# tempSensor.net
KiCad netlist of a schematic drawn in EAGLE
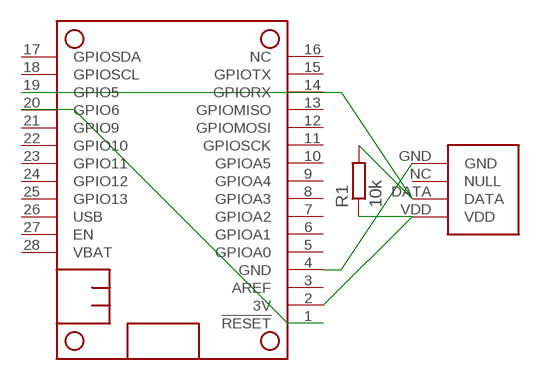
[diagram p0: schematic, sheet 1]

(export (version "E")
  (design (tool "Eeschema 10.0.6"))
  (components
    (comp (ref "MS1")
      (value "FEATHERWING_NODIM")
      (footprint "eagle-import:FEATHERWING_DIM")
      (libsource (lib "eagle-import") (part "FEATHERWING_NODIM"))
    )
    (comp (ref "R1")
      (value "10k")
      (footprint "eagle-import:0207_10")
      (libsource (lib "eagle-import") (part "R-EU_0207/10"))
    )
    (comp (ref "U$1")
      (value "DHT22")
      (footprint "eagle-import:DHT22")
      (libsource (lib "eagle-import") (part "DHT22"))
    )
  )
  (nets
    (net (code "1") (name "/USB") (class "Default")
      (node (ref "MS1") (pin "26") (pinfunction "USB_26") (pintype "power_in"))
    )
    (net (code "2") (name "/VBAT") (class "Default")
      (node (ref "MS1") (pin "28") (pinfunction "VBAT_28") (pintype "power_in"))
    )
    (net (code "3") (name "Net-(MS1-3V)") (class "Default")
      (node (ref "MS1") (pin "2") (pinfunction "3V_2") (pintype "power_in"))
      (node (ref "R1") (pin "1") (pinfunction "1_1") (pintype "passive"))
      (node (ref "U$1") (pin "VDD") (pinfunction "VDD_VDD") (pintype "power_in"))
    )
    (net (code "4") (name "Net-(MS1-GND)") (class "Default")
      (node (ref "MS1") (pin "4") (pinfunction "GND_4") (pintype "power_in"))
      (node (ref "U$1") (pin "GND") (pinfunction "GND_GND") (pintype "power_in"))
    )
    (net (code "5") (name "Net-(MS1-GPIO5)") (class "Default")
      (node (ref "MS1") (pin "19") (pinfunction "GPIO5_19") (pintype "bidirectional"))
      (node (ref "R1") (pin "2") (pinfunction "2_2") (pintype "passive"))
      (node (ref "U$1") (pin "DATA") (pinfunction "DATA_DATA") (pintype "output"))
    )
    (net (code "6") (name "Net-(MS1-GPIO6)") (class "Default")
      (node (ref "MS1") (pin "1") (pinfunction "~{RESET}_1") (pintype "input"))
      (node (ref "MS1") (pin "20") (pinfunction "GPIO6_20") (pintype "bidirectional"))
    )
    (net (code "7") (name "unconnected-(MS1-AREF-Pad3)") (class "Default")
      (node (ref "MS1") (pin "3") (pinfunction "AREF_3") (pintype "passive"))
    )
    (net (code "8") (name "unconnected-(MS1-EN-Pad27)") (class "Default")
      (node (ref "MS1") (pin "27") (pinfunction "EN_27") (pintype "passive"))
    )
    (net (code "9") (name "unconnected-(MS1-GPIO9-Pad21)") (class "Default")
      (node (ref "MS1") (pin "21") (pinfunction "GPIO9_21") (pintype "bidirectional"))
    )
    (net (code "10") (name "unconnected-(MS1-GPIO10-Pad22)") (class "Default")
      (node (ref "MS1") (pin "22") (pinfunction "GPIO10_22") (pintype "bidirectional"))
    )
    (net (code "11") (name "unconnected-(MS1-GPIO11-Pad23)") (class "Default")
      (node (ref "MS1") (pin "23") (pinfunction "GPIO11_23") (pintype "bidirectional"))
    )
    (net (code "12") (name "unconnected-(MS1-GPIO12-Pad24)") (class "Default")
      (node (ref "MS1") (pin "24") (pinfunction "GPIO12_24") (pintype "bidirectional"))
    )
    (net (code "13") (name "unconnected-(MS1-GPIO13-Pad25)") (class "Default")
      (node (ref "MS1") (pin "25") (pinfunction "GPIO13_25") (pintype "bidirectional"))
    )
    (net (code "14") (name "unconnected-(MS1-GPIOA0-Pad5)") (class "Default")
      (node (ref "MS1") (pin "5") (pinfunction "GPIOA0_5") (pintype "bidirectional"))
    )
    (net (code "15") (name "unconnected-(MS1-GPIOA1-Pad6)") (class "Default")
      (node (ref "MS1") (pin "6") (pinfunction "GPIOA1_6") (pintype "bidirectional"))
    )
    (net (code "16") (name "unconnected-(MS1-GPIOA2-Pad7)") (class "Default")
      (node (ref "MS1") (pin "7") (pinfunction "GPIOA2_7") (pintype "bidirectional"))
    )
    (net (code "17") (name "unconnected-(MS1-GPIOA3-Pad8)") (class "Default")
      (node (ref "MS1") (pin "8") (pinfunction "GPIOA3_8") (pintype "bidirectional"))
    )
    (net (code "18") (name "unconnected-(MS1-GPIOA4-Pad9)") (class "Default")
      (node (ref "MS1") (pin "9") (pinfunction "GPIOA4_9") (pintype "bidirectional"))
    )
    (net (code "19") (name "unconnected-(MS1-GPIOA5-Pad10)") (class "Default")
      (node (ref "MS1") (pin "10") (pinfunction "GPIOA5_10") (pintype "bidirectional"))
    )
    (net (code "20") (name "unconnected-(MS1-GPIOMISO-Pad13)") (class "Default")
      (node (ref "MS1") (pin "13") (pinfunction "GPIOMISO_13") (pintype "bidirectional"))
    )
    (net (code "21") (name "unconnected-(MS1-GPIOMOSI-Pad12)") (class "Default")
      (node (ref "MS1") (pin "12") (pinfunction "GPIOMOSI_12") (pintype "bidirectional"))
    )
    (net (code "22") (name "unconnected-(MS1-GPIORX-Pad14)") (class "Default")
      (node (ref "MS1") (pin "14") (pinfunction "GPIORX_14") (pintype "bidirectional"))
    )
    (net (code "23") (name "unconnected-(MS1-GPIOSCK-Pad11)") (class "Default")
      (node (ref "MS1") (pin "11") (pinfunction "GPIOSCK_11") (pintype "bidirectional"))
    )
    (net (code "24") (name "unconnected-(MS1-GPIOSCL-Pad18)") (class "Default")
      (node (ref "MS1") (pin "18") (pinfunction "GPIOSCL_18") (pintype "bidirectional"))
    )
    (net (code "25") (name "unconnected-(MS1-GPIOSDA-Pad17)") (class "Default")
      (node (ref "MS1") (pin "17") (pinfunction "GPIOSDA_17") (pintype "bidirectional"))
    )
    (net (code "26") (name "unconnected-(MS1-GPIOTX-Pad15)") (class "Default")
      (node (ref "MS1") (pin "15") (pinfunction "GPIOTX_15") (pintype "bidirectional"))
    )
    (net (code "27") (name "unconnected-(MS1-NC-Pad16)") (class "Default")
      (node (ref "MS1") (pin "16") (pinfunction "NC_16") (pintype "passive"))
    )
    (net (code "28") (name "unconnected-(U$1-NULL-PadNC)") (class "Default")
      (node (ref "U$1") (pin "NC") (pinfunction "NULL_NC") (pintype "no_connect"))
    )
  )
)
